# signal-board.net
KiCad netlist of a schematic drawn in EAGLE
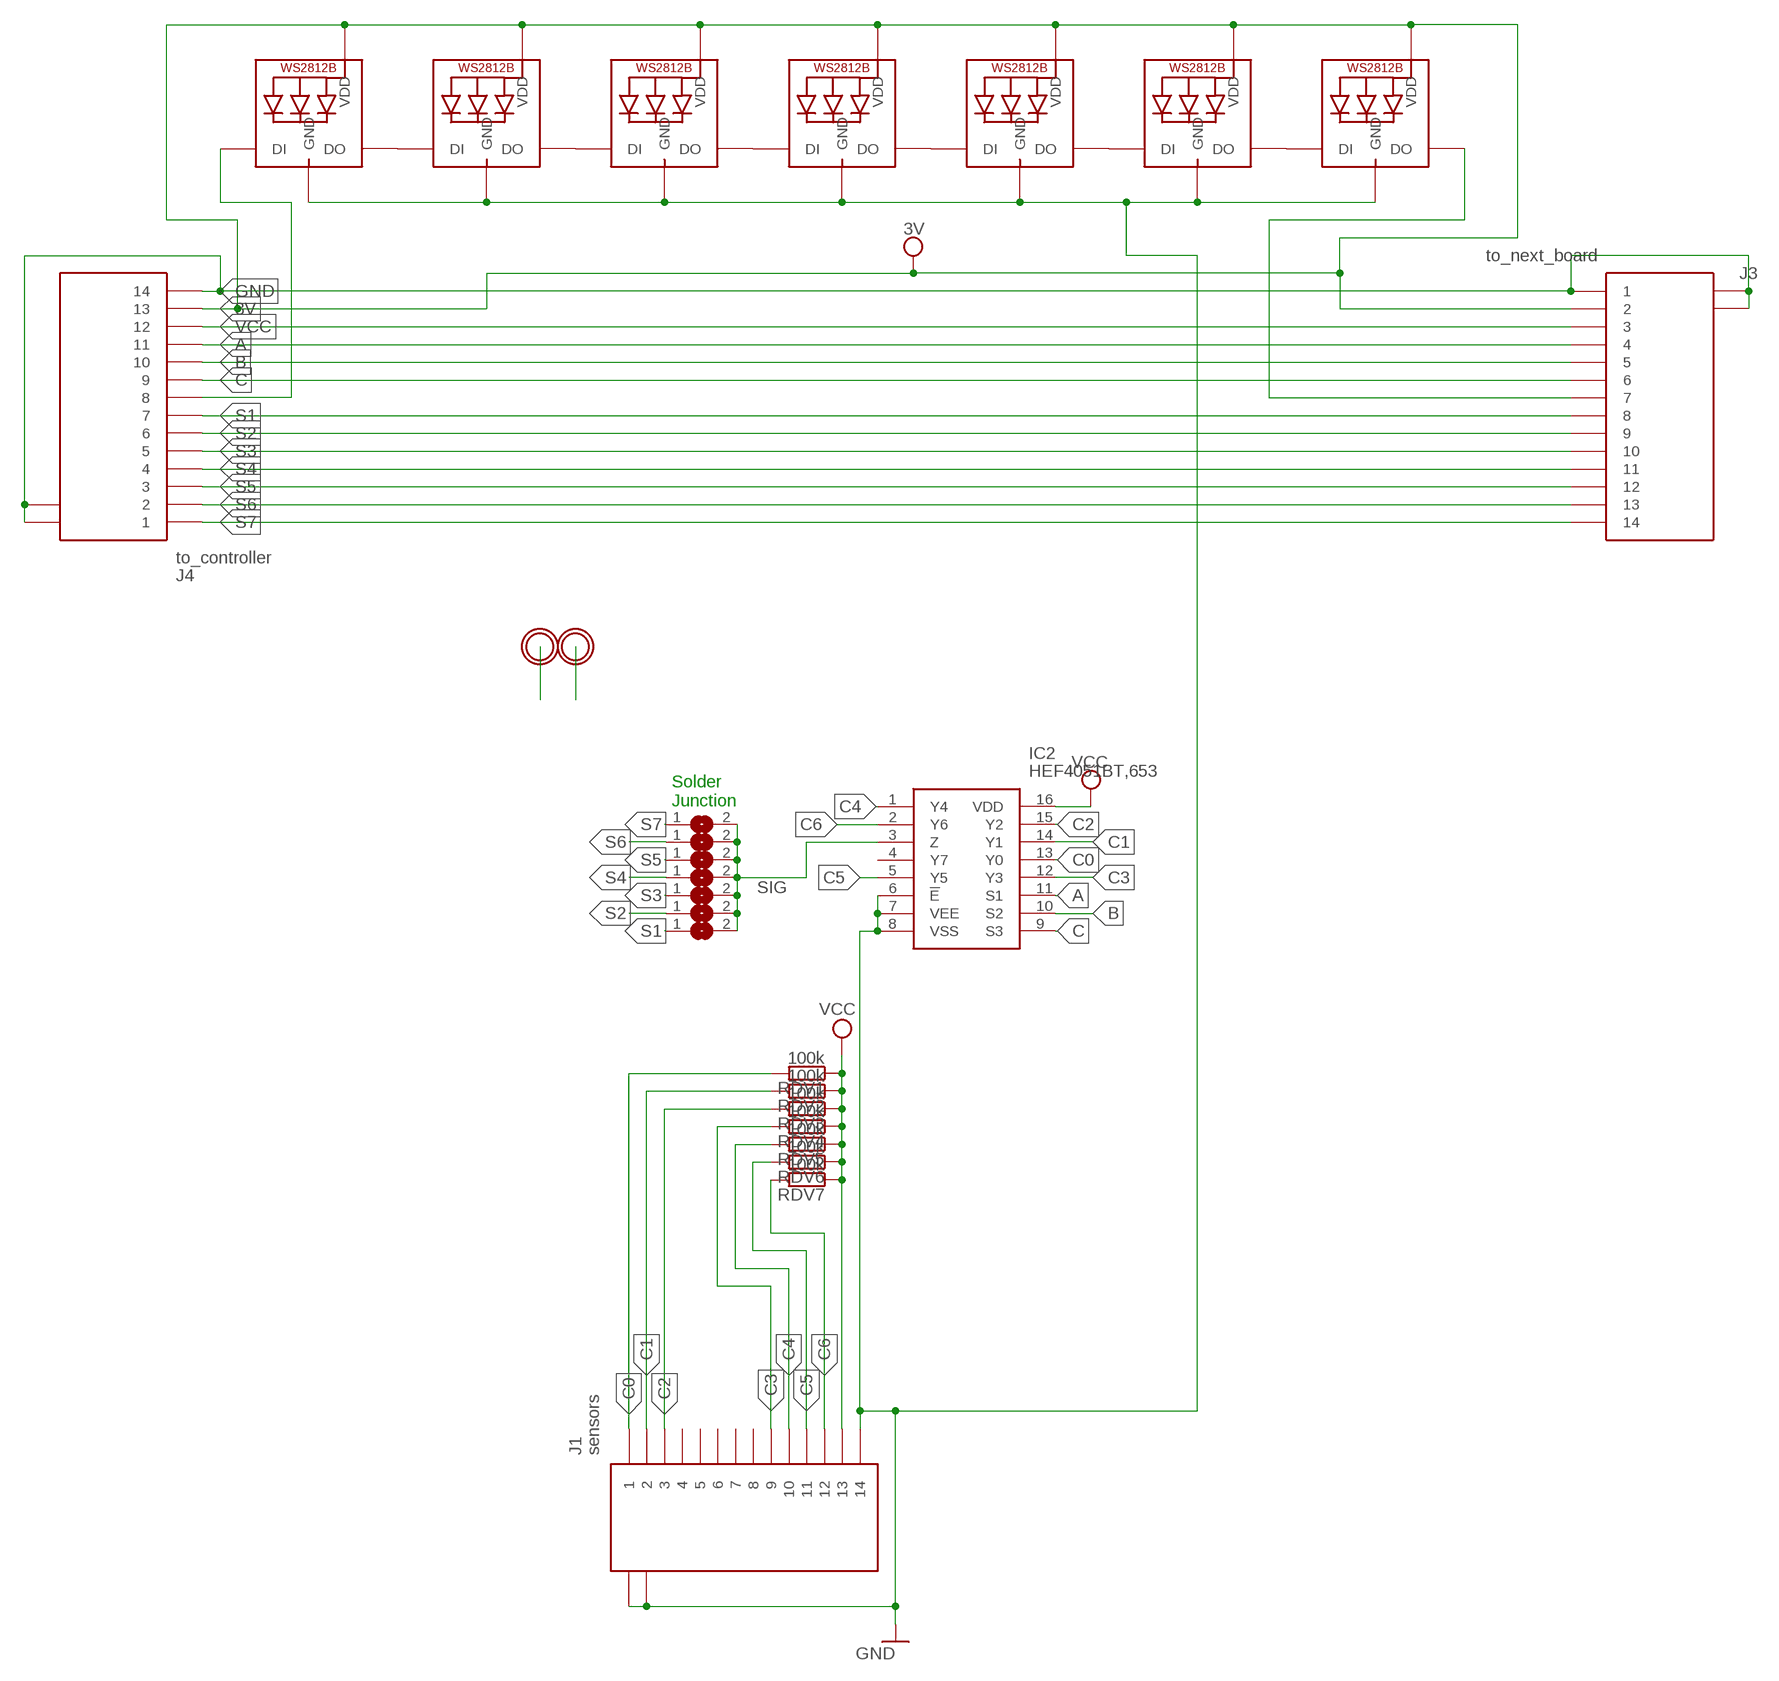
[diagram p0: schematic, sheet 1]

(export (version "E")
  (design (tool "Eeschema 10.0.6"))
  (components
    (comp (ref "IC2")
      (value "HEF4051BT,653")
      (footprint "eagle-import:HEF4051BT653")
      (fields (field (name "MOUSER_PART_NUMBER") "771-HEF4051BTD-T"))
      (libsource (lib "eagle-import") (part "HEF4051BT,653"))
    )
    (comp (ref "J1")
      (value "sensors")
      (footprint "eagle-import:686114148922")
      (fields
        (field (name "MANUFACTURER_PART_NUMBER") "686114148922")
        (field (name "MOUSER_PART_NUMBER") "710-686114148922")
      )
      (libsource (lib "eagle-import") (part "686114148922"))
    )
    (comp (ref "J3")
      (value "to_next_board")
      (footprint "eagle-import:686114148922")
      (fields
        (field (name "MANUFACTURER_PART_NUMBER") "686114148922")
        (field (name "MOUSER_PART_NUMBER") "710-686114148922")
      )
      (libsource (lib "eagle-import") (part "686114148922"))
    )
    (comp (ref "J4")
      (value "to_controller")
      (footprint "eagle-import:686114148922")
      (fields
        (field (name "MANUFACTURER_PART_NUMBER") "686114148922")
        (field (name "MOUSER_PART_NUMBER") "710-686114148922")
      )
      (libsource (lib "eagle-import") (part "686114148922"))
    )
    (comp (ref "LED1")
      (value "WS2812B3535")
      (footprint "eagle-import:LED3535")
      (libsource (lib "eagle-import") (part "WS2812B3535"))
    )
    (comp (ref "LED2")
      (value "WS2812B3535")
      (footprint "eagle-import:LED3535")
      (libsource (lib "eagle-import") (part "WS2812B3535"))
    )
    (comp (ref "LED3")
      (value "WS2812B3535")
      (footprint "eagle-import:LED3535")
      (libsource (lib "eagle-import") (part "WS2812B3535"))
    )
    (comp (ref "LED4")
      (value "WS2812B3535")
      (footprint "eagle-import:LED3535")
      (libsource (lib "eagle-import") (part "WS2812B3535"))
    )
    (comp (ref "LED5")
      (value "WS2812B3535")
      (footprint "eagle-import:LED3535")
      (libsource (lib "eagle-import") (part "WS2812B3535"))
    )
    (comp (ref "LED6")
      (value "WS2812B3535")
      (footprint "eagle-import:LED3535")
      (libsource (lib "eagle-import") (part "WS2812B3535"))
    )
    (comp (ref "LED7")
      (value "WS2812B3535")
      (footprint "eagle-import:LED3535")
      (libsource (lib "eagle-import") (part "WS2812B3535"))
    )
    (comp (ref "RDV1")
      (value "100k")
      (footprint "eagle-import:R0805")
      (libsource (lib "eagle-import") (part "R-EU_R0805"))
    )
    (comp (ref "RDV2")
      (value "100k")
      (footprint "eagle-import:R0805")
      (libsource (lib "eagle-import") (part "R-EU_R0805"))
    )
    (comp (ref "RDV3")
      (value "100k")
      (footprint "eagle-import:R0805")
      (libsource (lib "eagle-import") (part "R-EU_R0805"))
    )
    (comp (ref "RDV4")
      (value "100k")
      (footprint "eagle-import:R0805")
      (libsource (lib "eagle-import") (part "R-EU_R0805"))
    )
    (comp (ref "RDV5")
      (value "100k")
      (footprint "eagle-import:R0805")
      (libsource (lib "eagle-import") (part "R-EU_R0805"))
    )
    (comp (ref "RDV6")
      (value "100k")
      (footprint "eagle-import:R0805")
      (libsource (lib "eagle-import") (part "R-EU_R0805"))
    )
    (comp (ref "RDV7")
      (value "100k")
      (footprint "eagle-import:R0805")
      (libsource (lib "eagle-import") (part "R-EU_R0805"))
    )
    (comp (ref "SJ1") (value "SJ") (footprint "eagle-import:SJ") (libsource (lib "eagle-import") (part "SJ")))
    (comp (ref "SJ2") (value "SJ") (footprint "eagle-import:SJ") (libsource (lib "eagle-import") (part "SJ")))
    (comp (ref "SJ3") (value "SJ") (footprint "eagle-import:SJ") (libsource (lib "eagle-import") (part "SJ")))
    (comp (ref "SJ4") (value "SJ") (footprint "eagle-import:SJ") (libsource (lib "eagle-import") (part "SJ")))
    (comp (ref "SJ5") (value "SJ") (footprint "eagle-import:SJ") (libsource (lib "eagle-import") (part "SJ")))
    (comp (ref "SJ6") (value "SJ") (footprint "eagle-import:SJ") (libsource (lib "eagle-import") (part "SJ")))
    (comp (ref "SJ7") (value "SJ") (footprint "eagle-import:SJ") (libsource (lib "eagle-import") (part "SJ")))
    (comp (ref "U$1")
      (value "MICROBUILDER_MOUNTINGHOLEMICROBUILDER_MOUNTINGHOL_4.0")
      (footprint "eagle-import:MICROBUILDER_MOUNTINGHOLE_4.0_PLATEDTHIN")
      (libsource (lib "eagle-import") (part "MICROBUILDER_MOUNTINGHOLEMICROBUILDER_MOUNTINGHOL_4.0"))
    )
    (comp (ref "U$2")
      (value "MICROBUILDER_MOUNTINGHOLEMICROBUILDER_MOUNTINGHOL_4.0")
      (footprint "eagle-import:MICROBUILDER_MOUNTINGHOLE_4.0_PLATEDTHIN")
      (libsource (lib "eagle-import") (part "MICROBUILDER_MOUNTINGHOLEMICROBUILDER_MOUNTINGHOL_4.0"))
    )
  )
  (nets
    (net (code "1") (name "/SIG") (class "Default")
      (node (ref "IC2") (pin "3") (pinfunction "Z_3") (pintype "bidirectional"))
      (node (ref "SJ1") (pin "2") (pinfunction "2_2") (pintype "passive"))
      (node (ref "SJ2") (pin "2") (pinfunction "2_2") (pintype "passive"))
      (node (ref "SJ3") (pin "2") (pinfunction "2_2") (pintype "passive"))
      (node (ref "SJ4") (pin "2") (pinfunction "2_2") (pintype "passive"))
      (node (ref "SJ5") (pin "2") (pinfunction "2_2") (pintype "passive"))
      (node (ref "SJ6") (pin "2") (pinfunction "2_2") (pintype "passive"))
      (node (ref "SJ7") (pin "2") (pinfunction "2_2") (pintype "passive"))
    )
    (net (code "2") (name "3V") (class "Default")
      (node (ref "J3") (pin "2") (pinfunction "2_2") (pintype "bidirectional"))
      (node (ref "J4") (pin "13") (pinfunction "13_13") (pintype "bidirectional"))
      (node (ref "LED1") (pin "2") (pinfunction "VDD_2") (pintype "power_in"))
      (node (ref "LED2") (pin "2") (pinfunction "VDD_2") (pintype "power_in"))
      (node (ref "LED3") (pin "2") (pinfunction "VDD_2") (pintype "power_in"))
      (node (ref "LED4") (pin "2") (pinfunction "VDD_2") (pintype "power_in"))
      (node (ref "LED5") (pin "2") (pinfunction "VDD_2") (pintype "power_in"))
      (node (ref "LED6") (pin "2") (pinfunction "VDD_2") (pintype "power_in"))
      (node (ref "LED7") (pin "2") (pinfunction "VDD_2") (pintype "power_in"))
    )
    (net (code "3") (name "A") (class "Default")
      (node (ref "IC2") (pin "11") (pinfunction "S1_11") (pintype "bidirectional"))
      (node (ref "J3") (pin "4") (pinfunction "4_4") (pintype "bidirectional"))
      (node (ref "J4") (pin "11") (pinfunction "11_11") (pintype "bidirectional"))
    )
    (net (code "4") (name "B") (class "Default")
      (node (ref "IC2") (pin "10") (pinfunction "S2_10") (pintype "bidirectional"))
      (node (ref "J3") (pin "5") (pinfunction "5_5") (pintype "bidirectional"))
      (node (ref "J4") (pin "10") (pinfunction "10_10") (pintype "bidirectional"))
    )
    (net (code "5") (name "C") (class "Default")
      (node (ref "IC2") (pin "9") (pinfunction "S3_9") (pintype "bidirectional"))
      (node (ref "J3") (pin "6") (pinfunction "6_6") (pintype "bidirectional"))
      (node (ref "J4") (pin "9") (pinfunction "9_9") (pintype "bidirectional"))
    )
    (net (code "6") (name "C0") (class "Default")
      (node (ref "IC2") (pin "13") (pinfunction "Y0_13") (pintype "bidirectional"))
      (node (ref "J1") (pin "1") (pinfunction "1_1") (pintype "bidirectional"))
      (node (ref "RDV1") (pin "2") (pinfunction "2_2") (pintype "passive"))
    )
    (net (code "7") (name "C1") (class "Default")
      (node (ref "IC2") (pin "14") (pinfunction "Y1_14") (pintype "bidirectional"))
      (node (ref "J1") (pin "2") (pinfunction "2_2") (pintype "bidirectional"))
      (node (ref "RDV2") (pin "2") (pinfunction "2_2") (pintype "passive"))
    )
    (net (code "8") (name "C2") (class "Default")
      (node (ref "IC2") (pin "15") (pinfunction "Y2_15") (pintype "bidirectional"))
      (node (ref "J1") (pin "3") (pinfunction "3_3") (pintype "bidirectional"))
      (node (ref "RDV3") (pin "2") (pinfunction "2_2") (pintype "passive"))
    )
    (net (code "9") (name "C3") (class "Default")
      (node (ref "IC2") (pin "12") (pinfunction "Y3_12") (pintype "bidirectional"))
      (node (ref "J1") (pin "9") (pinfunction "9_9") (pintype "bidirectional"))
      (node (ref "RDV4") (pin "2") (pinfunction "2_2") (pintype "passive"))
    )
    (net (code "10") (name "C4") (class "Default")
      (node (ref "IC2") (pin "1") (pinfunction "Y4_1") (pintype "bidirectional"))
      (node (ref "J1") (pin "10") (pinfunction "10_10") (pintype "bidirectional"))
      (node (ref "RDV5") (pin "2") (pinfunction "2_2") (pintype "passive"))
    )
    (net (code "11") (name "C5") (class "Default")
      (node (ref "IC2") (pin "5") (pinfunction "Y5_5") (pintype "bidirectional"))
      (node (ref "J1") (pin "11") (pinfunction "11_11") (pintype "bidirectional"))
      (node (ref "RDV6") (pin "2") (pinfunction "2_2") (pintype "passive"))
    )
    (net (code "12") (name "C6") (class "Default")
      (node (ref "IC2") (pin "2") (pinfunction "Y6_2") (pintype "bidirectional"))
      (node (ref "J1") (pin "12") (pinfunction "12_12") (pintype "bidirectional"))
      (node (ref "RDV7") (pin "2") (pinfunction "2_2") (pintype "passive"))
    )
    (net (code "13") (name "GND") (class "Default")
      (node (ref "IC2") (pin "6") (pinfunction "~{E}_6") (pintype "bidirectional"))
      (node (ref "IC2") (pin "7") (pinfunction "VEE_7") (pintype "bidirectional"))
      (node (ref "IC2") (pin "8") (pinfunction "VSS_8") (pintype "bidirectional"))
      (node (ref "J1") (pin "14") (pinfunction "14_14") (pintype "bidirectional"))
      (node (ref "J1") (pin "MP1") (pinfunction "MP1_MP1") (pintype "bidirectional"))
      (node (ref "J1") (pin "MP2") (pinfunction "MP2_MP2") (pintype "bidirectional"))
      (node (ref "J3") (pin "1") (pinfunction "1_1") (pintype "bidirectional"))
      (node (ref "J3") (pin "MP1") (pinfunction "MP1_MP1") (pintype "bidirectional"))
      (node (ref "J3") (pin "MP2") (pinfunction "MP2_MP2") (pintype "bidirectional"))
      (node (ref "J4") (pin "14") (pinfunction "14_14") (pintype "bidirectional"))
      (node (ref "J4") (pin "MP1") (pinfunction "MP1_MP1") (pintype "bidirectional"))
      (node (ref "J4") (pin "MP2") (pinfunction "MP2_MP2") (pintype "bidirectional"))
      (node (ref "LED1") (pin "4") (pinfunction "GND_4") (pintype "power_in"))
      (node (ref "LED2") (pin "4") (pinfunction "GND_4") (pintype "power_in"))
      (node (ref "LED3") (pin "4") (pinfunction "GND_4") (pintype "power_in"))
      (node (ref "LED4") (pin "4") (pinfunction "GND_4") (pintype "power_in"))
      (node (ref "LED5") (pin "4") (pinfunction "GND_4") (pintype "power_in"))
      (node (ref "LED6") (pin "4") (pinfunction "GND_4") (pintype "power_in"))
      (node (ref "LED7") (pin "4") (pinfunction "GND_4") (pintype "power_in"))
    )
    (net (code "14") (name "Net-(LED1-DI)") (class "Default")
      (node (ref "J4") (pin "8") (pinfunction "8_8") (pintype "bidirectional"))
      (node (ref "LED1") (pin "1") (pinfunction "DI_1") (pintype "input"))
    )
    (net (code "15") (name "Net-(LED1-DO)") (class "Default")
      (node (ref "LED1") (pin "3") (pinfunction "DO_3") (pintype "output"))
      (node (ref "LED2") (pin "1") (pinfunction "DI_1") (pintype "input"))
    )
    (net (code "16") (name "Net-(LED2-DO)") (class "Default")
      (node (ref "LED2") (pin "3") (pinfunction "DO_3") (pintype "output"))
      (node (ref "LED3") (pin "1") (pinfunction "DI_1") (pintype "input"))
    )
    (net (code "17") (name "Net-(LED3-DO)") (class "Default")
      (node (ref "LED3") (pin "3") (pinfunction "DO_3") (pintype "output"))
      (node (ref "LED4") (pin "1") (pinfunction "DI_1") (pintype "input"))
    )
    (net (code "18") (name "Net-(LED4-DO)") (class "Default")
      (node (ref "LED4") (pin "3") (pinfunction "DO_3") (pintype "output"))
      (node (ref "LED5") (pin "1") (pinfunction "DI_1") (pintype "input"))
    )
    (net (code "19") (name "Net-(LED5-DO)") (class "Default")
      (node (ref "LED5") (pin "3") (pinfunction "DO_3") (pintype "output"))
      (node (ref "LED6") (pin "1") (pinfunction "DI_1") (pintype "input"))
    )
    (net (code "20") (name "Net-(LED6-DO)") (class "Default")
      (node (ref "LED6") (pin "3") (pinfunction "DO_3") (pintype "output"))
      (node (ref "LED7") (pin "1") (pinfunction "DI_1") (pintype "input"))
    )
    (net (code "21") (name "Net-(LED7-DO)") (class "Default")
      (node (ref "J3") (pin "7") (pinfunction "7_7") (pintype "bidirectional"))
      (node (ref "LED7") (pin "3") (pinfunction "DO_3") (pintype "output"))
    )
    (net (code "22") (name "S1") (class "Default")
      (node (ref "J3") (pin "8") (pinfunction "8_8") (pintype "bidirectional"))
      (node (ref "J4") (pin "7") (pinfunction "7_7") (pintype "bidirectional"))
      (node (ref "SJ1") (pin "1") (pinfunction "1_1") (pintype "passive"))
    )
    (net (code "23") (name "S2") (class "Default")
      (node (ref "J3") (pin "9") (pinfunction "9_9") (pintype "bidirectional"))
      (node (ref "J4") (pin "6") (pinfunction "6_6") (pintype "bidirectional"))
      (node (ref "SJ2") (pin "1") (pinfunction "1_1") (pintype "passive"))
    )
    (net (code "24") (name "S3") (class "Default")
      (node (ref "J3") (pin "10") (pinfunction "10_10") (pintype "bidirectional"))
      (node (ref "J4") (pin "5") (pinfunction "5_5") (pintype "bidirectional"))
      (node (ref "SJ3") (pin "1") (pinfunction "1_1") (pintype "passive"))
    )
    (net (code "25") (name "S4") (class "Default")
      (node (ref "J3") (pin "11") (pinfunction "11_11") (pintype "bidirectional"))
      (node (ref "J4") (pin "4") (pinfunction "4_4") (pintype "bidirectional"))
      (node (ref "SJ4") (pin "1") (pinfunction "1_1") (pintype "passive"))
    )
    (net (code "26") (name "S5") (class "Default")
      (node (ref "J3") (pin "12") (pinfunction "12_12") (pintype "bidirectional"))
      (node (ref "J4") (pin "3") (pinfunction "3_3") (pintype "bidirectional"))
      (node (ref "SJ5") (pin "1") (pinfunction "1_1") (pintype "passive"))
    )
    (net (code "27") (name "S6") (class "Default")
      (node (ref "J3") (pin "13") (pinfunction "13_13") (pintype "bidirectional"))
      (node (ref "J4") (pin "2") (pinfunction "2_2") (pintype "bidirectional"))
      (node (ref "SJ6") (pin "1") (pinfunction "1_1") (pintype "passive"))
    )
    (net (code "28") (name "S7") (class "Default")
      (node (ref "J3") (pin "14") (pinfunction "14_14") (pintype "bidirectional"))
      (node (ref "J4") (pin "1") (pinfunction "1_1") (pintype "bidirectional"))
      (node (ref "SJ7") (pin "1") (pinfunction "1_1") (pintype "passive"))
    )
    (net (code "29") (name "VCC") (class "Default")
      (node (ref "IC2") (pin "16") (pinfunction "VDD_16") (pintype "bidirectional"))
      (node (ref "J1") (pin "13") (pinfunction "13_13") (pintype "bidirectional"))
      (node (ref "J3") (pin "3") (pinfunction "3_3") (pintype "bidirectional"))
      (node (ref "J4") (pin "12") (pinfunction "12_12") (pintype "bidirectional"))
      (node (ref "RDV1") (pin "1") (pinfunction "1_1") (pintype "passive"))
      (node (ref "RDV2") (pin "1") (pinfunction "1_1") (pintype "passive"))
      (node (ref "RDV3") (pin "1") (pinfunction "1_1") (pintype "passive"))
      (node (ref "RDV4") (pin "1") (pinfunction "1_1") (pintype "passive"))
      (node (ref "RDV5") (pin "1") (pinfunction "1_1") (pintype "passive"))
      (node (ref "RDV6") (pin "1") (pinfunction "1_1") (pintype "passive"))
      (node (ref "RDV7") (pin "1") (pinfunction "1_1") (pintype "passive"))
    )
    (net (code "30") (name "unconnected-(IC2-Y7-Pad4)") (class "Default")
      (node (ref "IC2") (pin "4") (pinfunction "Y7_4") (pintype "bidirectional"))
    )
    (net (code "31") (name "unconnected-(J1-Pad4)") (class "Default")
      (node (ref "J1") (pin "4") (pinfunction "4_4") (pintype "bidirectional"))
    )
    (net (code "32") (name "unconnected-(J1-Pad5)") (class "Default")
      (node (ref "J1") (pin "5") (pinfunction "5_5") (pintype "bidirectional"))
    )
    (net (code "33") (name "unconnected-(J1-Pad6)") (class "Default")
      (node (ref "J1") (pin "6") (pinfunction "6_6") (pintype "bidirectional"))
    )
    (net (code "34") (name "unconnected-(J1-Pad7)") (class "Default")
      (node (ref "J1") (pin "7") (pinfunction "7_7") (pintype "bidirectional"))
    )
    (net (code "35") (name "unconnected-(J1-Pad8)") (class "Default")
      (node (ref "J1") (pin "8") (pinfunction "8_8") (pintype "bidirectional"))
    )
  )
)
